# Metro_THM_LDO_Rev_B.net
KiCad netlist of a schematic drawn in EAGLE
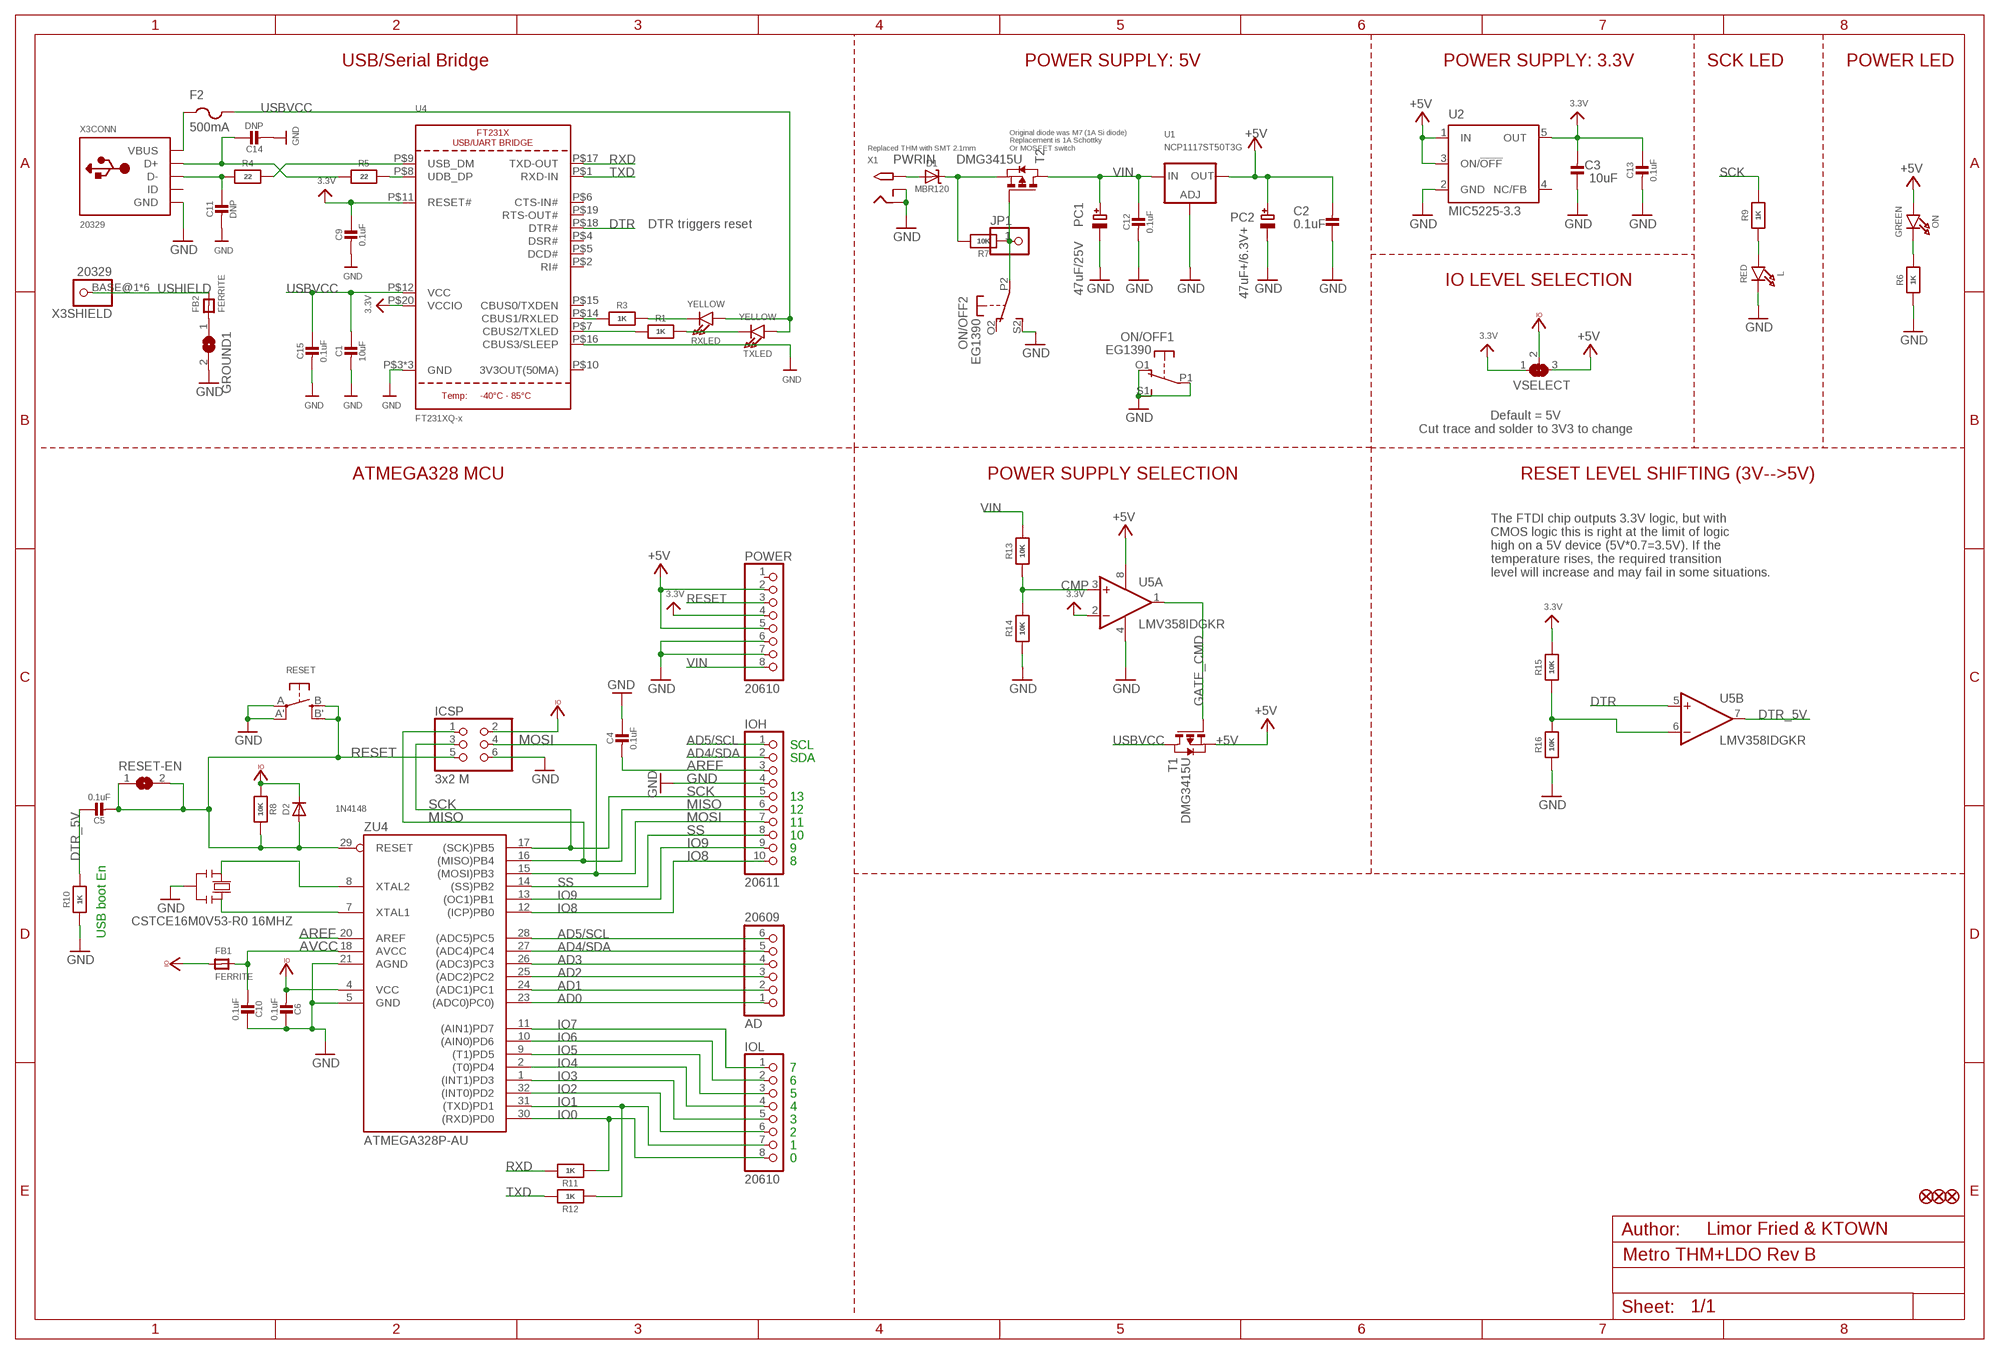
[diagram p0: schematic, sheet 1]

(export (version "E")
  (design (tool "Eeschema 10.0.6"))
  (components
    (comp (ref "AD")
      (value "20609")
      (footprint "eagle-import:1X06_OVAL")
      (libsource (lib "eagle-import") (part "HEADER-1X6"))
    )
    (comp (ref "C1")
      (value "10uF")
      (footprint "eagle-import:0805-NO")
      (libsource (lib "eagle-import") (part "CAP_CERAMIC0805-NOOUTLINE"))
    )
    (comp (ref "C2")
      (value "0.1uF")
      (footprint "eagle-import:0805-NO")
      (libsource (lib "eagle-import") (part "CAP_CERAMIC0805-NOOUTLINE"))
    )
    (comp (ref "C3")
      (value "10uF")
      (footprint "eagle-import:0805-NO")
      (libsource (lib "eagle-import") (part "CAP_CERAMIC0805-NOOUTLINE"))
    )
    (comp (ref "C4")
      (value "0.1uF")
      (footprint "eagle-import:0805-NO")
      (libsource (lib "eagle-import") (part "CAP_CERAMIC0805-NOOUTLINE"))
    )
    (comp (ref "C5")
      (value "0.1uF")
      (footprint "eagle-import:0805-NO")
      (libsource (lib "eagle-import") (part "CAP_CERAMIC0805-NOOUTLINE"))
    )
    (comp (ref "C6")
      (value "0.1uF")
      (footprint "eagle-import:0805-NO")
      (libsource (lib "eagle-import") (part "CAP_CERAMIC0805-NOOUTLINE"))
    )
    (comp (ref "C9")
      (value "0.1uF")
      (footprint "eagle-import:0805-NO")
      (libsource (lib "eagle-import") (part "CAP_CERAMIC0805-NOOUTLINE"))
    )
    (comp (ref "C10")
      (value "0.1uF")
      (footprint "eagle-import:0805_10MGAP")
      (libsource (lib "eagle-import") (part "CAP_CERAMIC0805_10MGAP"))
    )
    (comp (ref "C11")
      (value "DNP")
      (footprint "eagle-import:0805-NO")
      (libsource (lib "eagle-import") (part "CAP_CERAMIC0805-NOOUTLINE"))
    )
    (comp (ref "C12")
      (value "0.1uF")
      (footprint "eagle-import:0805-NO")
      (libsource (lib "eagle-import") (part "CAP_CERAMIC0805-NOOUTLINE"))
    )
    (comp (ref "C13")
      (value "0.1uF")
      (footprint "eagle-import:0805-NO")
      (libsource (lib "eagle-import") (part "CAP_CERAMIC0805-NOOUTLINE"))
    )
    (comp (ref "C14")
      (value "DNP")
      (footprint "eagle-import:0805-NO")
      (libsource (lib "eagle-import") (part "CAP_CERAMIC0805-NOOUTLINE"))
    )
    (comp (ref "C15")
      (value "0.1uF")
      (footprint "eagle-import:0805-NO")
      (libsource (lib "eagle-import") (part "CAP_CERAMIC0805-NOOUTLINE"))
    )
    (comp (ref "D1")
      (value "MBR120")
      (footprint "eagle-import:SOD-123")
      (libsource (lib "eagle-import") (part "DIODE-SCHOTTKYSOD-123"))
    )
    (comp (ref "D2")
      (value "1N4148")
      (footprint "eagle-import:SOD-323")
      (libsource (lib "eagle-import") (part "DIODESOD-323"))
    )
    (comp (ref "F2")
      (value "500mA")
      (footprint "eagle-import:R1206")
      (libsource (lib "eagle-import") (part "PTCFUSE-1206"))
    )
    (comp (ref "FB1")
      (value "FERRITE")
      (footprint "eagle-import:0805-NO")
      (libsource (lib "eagle-import") (part "FERRITE-0805NO"))
    )
    (comp (ref "FB2")
      (value "FERRITE")
      (footprint "eagle-import:0805-NO")
      (libsource (lib "eagle-import") (part "FERRITE-0805NO"))
    )
    (comp (ref "FD1")
      (value "FIDUCIAL\"\"")
      (footprint "eagle-import:FIDUCIAL_1MM")
      (libsource (lib "eagle-import") (part "FIDUCIAL{dblquote}{dblquote}"))
    )
    (comp (ref "FD2")
      (value "FIDUCIAL\"\"")
      (footprint "eagle-import:FIDUCIAL_1MM")
      (libsource (lib "eagle-import") (part "FIDUCIAL{dblquote}{dblquote}"))
    )
    (comp (ref "FD3")
      (value "FIDUCIAL\"\"")
      (footprint "eagle-import:FIDUCIAL_1MM")
      (libsource (lib "eagle-import") (part "FIDUCIAL{dblquote}{dblquote}"))
    )
    (comp (ref "GROUND1")
      (value "SJ")
      (footprint "eagle-import:SJ")
      (libsource (lib "eagle-import") (part "SJ"))
    )
    (comp (ref "ICSP")
      (value "3x2 M")
      (footprint "eagle-import:2X03_ROUND_70MIL")
      (libsource (lib "eagle-import") (part "HEADER-2X3"))
    )
    (comp (ref "IOH")
      (value "20611")
      (footprint "eagle-import:1X10_OVAL")
      (libsource (lib "eagle-import") (part "HEADER-1X10"))
    )
    (comp (ref "IOL")
      (value "20610")
      (footprint "eagle-import:1X08_OVAL")
      (libsource (lib "eagle-import") (part "HEADER-1X8"))
    )
    (comp (ref "JP1")
      (value "HEADER-1X1ROUND")
      (footprint "eagle-import:1X01_ROUND")
      (libsource (lib "eagle-import") (part "HEADER-1X1ROUND"))
    )
    (comp (ref "L")
      (value "RED")
      (footprint "eagle-import:CHIPLED_0805_NOOUTLINE")
      (libsource (lib "eagle-import") (part "LED0805_NOOUTLINE"))
    )
    (comp (ref "ON")
      (value "GREEN")
      (footprint "eagle-import:CHIPLED_0805_NOOUTLINE")
      (libsource (lib "eagle-import") (part "LED0805_NOOUTLINE"))
    )
    (comp (ref "ON/OFF")
      (value "EG1390")
      (footprint "eagle-import:EG1390")
      (libsource (lib "eagle-import") (part "DPDT-EG1390"))
    )
    (comp (ref "PC1")
      (value "47uF/25V")
      (footprint "eagle-import:PANASONIC_D")
      (libsource (lib "eagle-import") (part "CAP_ELECTROLYTICPANASONIC_D"))
    )
    (comp (ref "PC2")
      (value "47uF+/6.3V+")
      (footprint "eagle-import:PANASONIC_D")
      (libsource (lib "eagle-import") (part "CAP_ELECTROLYTICPANASONIC_D"))
    )
    (comp (ref "POWER")
      (value "20610")
      (footprint "eagle-import:1X08_OVAL")
      (libsource (lib "eagle-import") (part "HEADER-1X8"))
    )
    (comp (ref "R1")
      (value "1K")
      (footprint "eagle-import:0805-NO")
      (libsource (lib "eagle-import") (part "RESISTOR0805_NOOUTLINE"))
    )
    (comp (ref "R3")
      (value "1K")
      (footprint "eagle-import:0805-NO")
      (libsource (lib "eagle-import") (part "RESISTOR0805_NOOUTLINE"))
    )
    (comp (ref "R4")
      (value "22")
      (footprint "eagle-import:0805-NO")
      (libsource (lib "eagle-import") (part "RESISTOR0805_NOOUTLINE"))
    )
    (comp (ref "R5")
      (value "22")
      (footprint "eagle-import:0805-NO")
      (libsource (lib "eagle-import") (part "RESISTOR0805_NOOUTLINE"))
    )
    (comp (ref "R6")
      (value "1K")
      (footprint "eagle-import:0805-NO")
      (libsource (lib "eagle-import") (part "RESISTOR0805_NOOUTLINE"))
    )
    (comp (ref "R7")
      (value "10K")
      (footprint "eagle-import:0805-NO")
      (libsource (lib "eagle-import") (part "RESISTOR0805_NOOUTLINE"))
    )
    (comp (ref "R8")
      (value "10K")
      (footprint "eagle-import:_0805MP")
      (libsource (lib "eagle-import") (part "RESISTOR_0805MP"))
    )
    (comp (ref "R9")
      (value "1K")
      (footprint "eagle-import:0805-NO")
      (libsource (lib "eagle-import") (part "RESISTOR0805_NOOUTLINE"))
    )
    (comp (ref "R10")
      (value "1K")
      (footprint "eagle-import:0805-NO")
      (libsource (lib "eagle-import") (part "RESISTOR0805_NOOUTLINE"))
    )
    (comp (ref "R11")
      (value "1K")
      (footprint "eagle-import:0805-NO")
      (libsource (lib "eagle-import") (part "RESISTOR0805_NOOUTLINE"))
    )
    (comp (ref "R12")
      (value "1K")
      (footprint "eagle-import:0805-NO")
      (libsource (lib "eagle-import") (part "RESISTOR0805_NOOUTLINE"))
    )
    (comp (ref "R13")
      (value "10K")
      (footprint "eagle-import:0805-NO")
      (libsource (lib "eagle-import") (part "RESISTOR0805_NOOUTLINE"))
    )
    (comp (ref "R14")
      (value "10K")
      (footprint "eagle-import:0805-NO")
      (libsource (lib "eagle-import") (part "RESISTOR0805_NOOUTLINE"))
    )
    (comp (ref "R15")
      (value "10K")
      (footprint "eagle-import:0805-NO")
      (libsource (lib "eagle-import") (part "RESISTOR0805_NOOUTLINE"))
    )
    (comp (ref "R16")
      (value "10K")
      (footprint "eagle-import:0805-NO")
      (libsource (lib "eagle-import") (part "RESISTOR0805_NOOUTLINE"))
    )
    (comp (ref "RESET")
      (value "SWITCH_TACT_SMT")
      (footprint "eagle-import:EVQ-Q2")
      (libsource (lib "eagle-import") (part "SWITCH_TACT_SMT"))
    )
    (comp (ref "RESET-EN")
      (value "SJ")
      (footprint "eagle-import:SJ")
      (libsource (lib "eagle-import") (part "SJ"))
    )
    (comp (ref "RXLED")
      (value "YELLOW")
      (footprint "eagle-import:CHIPLED_0805_NOOUTLINE")
      (libsource (lib "eagle-import") (part "LED0805_NOOUTLINE"))
    )
    (comp (ref "T1")
      (value "DMG3415U")
      (footprint "eagle-import:SOT-23")
      (libsource (lib "eagle-import") (part "PMOSSOT23"))
    )
    (comp (ref "T2")
      (value "DMG3415U")
      (footprint "eagle-import:SOT-23")
      (libsource (lib "eagle-import") (part "PMOSSOT23"))
    )
    (comp (ref "TXLED")
      (value "YELLOW")
      (footprint "eagle-import:CHIPLED_0805_NOOUTLINE")
      (libsource (lib "eagle-import") (part "LED0805_NOOUTLINE"))
    )
    (comp (ref "U1")
      (value "NCP1117ST50T3G")
      (footprint "eagle-import:SOT223-R")
      (libsource (lib "eagle-import") (part "LM1117SOT223-REFLOW"))
    )
    (comp (ref "U2")
      (value "MIC5225-3.3")
      (footprint "eagle-import:SOT23-DBV")
      (libsource (lib "eagle-import") (part "LP2985-XXDBVR33"))
    )
    (comp (ref "U4")
      (value "FT231XQ-x")
      (footprint "eagle-import:QFN20_4MM")
      (libsource (lib "eagle-import") (part "FT231X"))
    )
    (comp (ref "U5")
      (value "LMV358IDGKR")
      (footprint "eagle-import:MSOP08")
      (libsource (lib "eagle-import") (part "LMV358?MMX"))
    )
    (comp (ref "VSELECT")
      (value "SOLDERJUMPER_2WAY")
      (footprint "eagle-import:SOLDERJUMPER_2WAY_OPEN_NOPASTE")
      (libsource (lib "eagle-import") (part "SOLDERJUMPER_2WAY"))
    )
    (comp (ref "X1")
      (value "2.1MMJACKSMT")
      (footprint "eagle-import:DCJACK_2MM_SMT")
      (libsource (lib "eagle-import") (part "2.1MMJACKSMT"))
    )
    (comp (ref "X3")
      (value "20329")
      (footprint "eagle-import:4UCONN_20329")
      (libsource (lib "eagle-import") (part "USB_W_SHIELD_20329"))
    )
    (comp (ref "Y2")
      (value "CSTCE16M0V53-R0 16MHZ")
      (footprint "eagle-import:RESONATOR")
      (libsource (lib "eagle-import") (part "RESONATORMU"))
    )
    (comp (ref "ZU4")
      (value "ATMEGA328P-AU")
      (footprint "eagle-import:TQFP32-08")
      (libsource (lib "eagle-import") (part "ATMEGA328P-AU"))
    )
  )
  (nets
    (net (code "1") (name "+5V") (class "Default")
      (node (ref "C2") (pin "2") (pinfunction "2_2") (pintype "passive"))
      (node (ref "ON") (pin "A") (pinfunction "A_A") (pintype "passive"))
      (node (ref "PC2") (pin "+") (pinfunction "+_+") (pintype "passive"))
      (node (ref "POWER") (pin "2") (pinfunction "2_2") (pintype "passive"))
      (node (ref "POWER") (pin "5") (pinfunction "5_5") (pintype "passive"))
      (node (ref "T1") (pin "2") (pinfunction "S_2") (pintype "passive"))
      (node (ref "U1") (pin "2") (pinfunction "OUT_2") (pintype "passive"))
      (node (ref "U1") (pin "4") (pinfunction "OUT_4") (pintype "passive"))
      (node (ref "U2") (pin "1") (pinfunction "IN_1") (pintype "input"))
      (node (ref "U2") (pin "3") (pinfunction "ON/~{OFF}_3") (pintype "input"))
      (node (ref "U5") (pin "8") (pinfunction "V+_8") (pintype "power_in"))
      (node (ref "VSELECT") (pin "3") (pinfunction "3_3") (pintype "passive"))
    )
    (net (code "2") (name "/3V3OUT(50MA)") (class "Default")
      (node (ref "U4") (pin "P$10") (pinfunction "3V3OUT(50MA)_P$10") (pintype "power_in"))
    )
    (net (code "3") (name "/AD0") (class "Default")
      (node (ref "AD") (pin "1") (pinfunction "1_1") (pintype "passive"))
      (node (ref "ZU4") (pin "23") (pinfunction "(ADC0)PC0)_23") (pintype "bidirectional"))
    )
    (net (code "4") (name "/AD1") (class "Default")
      (node (ref "AD") (pin "2") (pinfunction "2_2") (pintype "passive"))
      (node (ref "ZU4") (pin "24") (pinfunction "(ADC1)PC1_24") (pintype "bidirectional"))
    )
    (net (code "5") (name "/AD2") (class "Default")
      (node (ref "AD") (pin "3") (pinfunction "3_3") (pintype "passive"))
      (node (ref "ZU4") (pin "25") (pinfunction "(ADC2)PC2_25") (pintype "bidirectional"))
    )
    (net (code "6") (name "/AD3") (class "Default")
      (node (ref "AD") (pin "4") (pinfunction "4_4") (pintype "passive"))
      (node (ref "ZU4") (pin "26") (pinfunction "(ADC3)PC3_26") (pintype "bidirectional"))
    )
    (net (code "7") (name "/AD4{slash}SDA") (class "Default")
      (node (ref "AD") (pin "5") (pinfunction "5_5") (pintype "passive"))
      (node (ref "IOH") (pin "2") (pinfunction "2_2") (pintype "passive"))
      (node (ref "ZU4") (pin "27") (pinfunction "(ADC4)PC4_27") (pintype "bidirectional"))
    )
    (net (code "8") (name "/AD5{slash}SCL") (class "Default")
      (node (ref "AD") (pin "6") (pinfunction "6_6") (pintype "passive"))
      (node (ref "IOH") (pin "1") (pinfunction "1_1") (pintype "passive"))
      (node (ref "ZU4") (pin "28") (pinfunction "(ADC5)PC5_28") (pintype "bidirectional"))
    )
    (net (code "9") (name "/AREF") (class "Default")
      (node (ref "C4") (pin "2") (pinfunction "2_2") (pintype "passive"))
      (node (ref "IOH") (pin "3") (pinfunction "3_3") (pintype "passive"))
      (node (ref "ZU4") (pin "20") (pinfunction "AREF_20") (pintype "passive"))
    )
    (net (code "10") (name "/AVCC") (class "Default")
      (node (ref "C10") (pin "2") (pinfunction "2_2") (pintype "passive"))
      (node (ref "FB1") (pin "2") (pinfunction "P$2_2") (pintype "passive"))
      (node (ref "ZU4") (pin "18") (pinfunction "AVCC_18") (pintype "power_in"))
    )
    (net (code "11") (name "/CMP") (class "Default")
      (node (ref "R13") (pin "1") (pinfunction "1_1") (pintype "passive"))
      (node (ref "R14") (pin "2") (pinfunction "2_2") (pintype "passive"))
      (node (ref "U5") (pin "3") (pinfunction "+IN_3") (pintype "input"))
    )
    (net (code "12") (name "/DTR") (class "Default")
      (node (ref "U4") (pin "P$18") (pinfunction "DTR#_P$18") (pintype "output"))
      (node (ref "U5") (pin "5") (pinfunction "+IN_5") (pintype "input"))
    )
    (net (code "13") (name "/DTR_5V") (class "Default")
      (node (ref "C5") (pin "1") (pinfunction "1_1") (pintype "passive"))
      (node (ref "R10") (pin "2") (pinfunction "2_2") (pintype "passive"))
      (node (ref "U5") (pin "7") (pinfunction "OUT_7") (pintype "output"))
    )
    (net (code "14") (name "/GATE_CMD") (class "Default")
      (node (ref "T1") (pin "3") (pinfunction "G_3") (pintype "passive"))
      (node (ref "U5") (pin "1") (pinfunction "OUT_1") (pintype "output"))
    )
    (net (code "15") (name "/IO0") (class "Default")
      (node (ref "IOL") (pin "8") (pinfunction "8_8") (pintype "passive"))
      (node (ref "R11") (pin "1") (pinfunction "1_1") (pintype "passive"))
      (node (ref "ZU4") (pin "30") (pinfunction "(RXD)PD0_30") (pintype "bidirectional"))
    )
    (net (code "16") (name "/IO1") (class "Default")
      (node (ref "IOL") (pin "7") (pinfunction "7_7") (pintype "passive"))
      (node (ref "R12") (pin "1") (pinfunction "1_1") (pintype "passive"))
      (node (ref "ZU4") (pin "31") (pinfunction "(TXD)PD1_31") (pintype "bidirectional"))
    )
    (net (code "17") (name "/IO2") (class "Default")
      (node (ref "IOL") (pin "6") (pinfunction "6_6") (pintype "passive"))
      (node (ref "ZU4") (pin "32") (pinfunction "(INT0)PD2_32") (pintype "bidirectional"))
    )
    (net (code "18") (name "/IO3") (class "Default")
      (node (ref "IOL") (pin "5") (pinfunction "5_5") (pintype "passive"))
      (node (ref "ZU4") (pin "1") (pinfunction "(INT1)PD3_1") (pintype "bidirectional"))
    )
    (net (code "19") (name "/IO4") (class "Default")
      (node (ref "IOL") (pin "4") (pinfunction "4_4") (pintype "passive"))
      (node (ref "ZU4") (pin "2") (pinfunction "(T0)PD4_2") (pintype "bidirectional"))
    )
    (net (code "20") (name "/IO5") (class "Default")
      (node (ref "IOL") (pin "3") (pinfunction "3_3") (pintype "passive"))
      (node (ref "ZU4") (pin "9") (pinfunction "(T1)PD5_9") (pintype "bidirectional"))
    )
    (net (code "21") (name "/IO6") (class "Default")
      (node (ref "IOL") (pin "2") (pinfunction "2_2") (pintype "passive"))
      (node (ref "ZU4") (pin "10") (pinfunction "(AIN0)PD6_10") (pintype "bidirectional"))
    )
    (net (code "22") (name "/IO7") (class "Default")
      (node (ref "IOL") (pin "1") (pinfunction "1_1") (pintype "passive"))
      (node (ref "ZU4") (pin "11") (pinfunction "(AIN1)PD7_11") (pintype "bidirectional"))
    )
    (net (code "23") (name "/IO8") (class "Default")
      (node (ref "IOH") (pin "10") (pinfunction "10_10") (pintype "passive"))
      (node (ref "ZU4") (pin "12") (pinfunction "(ICP)PB0_12") (pintype "bidirectional"))
    )
    (net (code "24") (name "/IO9") (class "Default")
      (node (ref "IOH") (pin "9") (pinfunction "9_9") (pintype "passive"))
      (node (ref "ZU4") (pin "13") (pinfunction "(OC1)PB1_13") (pintype "bidirectional"))
    )
    (net (code "25") (name "/MISO") (class "Default")
      (node (ref "ICSP") (pin "1") (pinfunction "1_1") (pintype "passive"))
      (node (ref "IOH") (pin "6") (pinfunction "6_6") (pintype "passive"))
      (node (ref "ZU4") (pin "16") (pinfunction "(MISO)PB4_16") (pintype "bidirectional"))
    )
    (net (code "26") (name "/MOSI") (class "Default")
      (node (ref "ICSP") (pin "4") (pinfunction "4_4") (pintype "passive"))
      (node (ref "IOH") (pin "7") (pinfunction "7_7") (pintype "passive"))
      (node (ref "ZU4") (pin "15") (pinfunction "(MOSI)PB3_15") (pintype "bidirectional"))
    )
    (net (code "27") (name "/PWRIN") (class "Default")
      (node (ref "D1") (pin "A") (pinfunction "A_A") (pintype "passive"))
      (node (ref "X1") (pin "PWR2") (pinfunction "TIP_PWR2") (pintype "bidirectional"))
    )
    (net (code "28") (name "/RESET") (class "Default")
      (node (ref "C5") (pin "2") (pinfunction "2_2") (pintype "passive"))
      (node (ref "D2") (pin "A") (pinfunction "A_A") (pintype "passive"))
      (node (ref "ICSP") (pin "5") (pinfunction "5_5") (pintype "passive"))
      (node (ref "POWER") (pin "3") (pinfunction "3_3") (pintype "passive"))
      (node (ref "R8") (pin "1") (pinfunction "1_1") (pintype "passive"))
      (node (ref "RESET") (pin "B") (pinfunction "S_B") (pintype "passive"))
      (node (ref "RESET") (pin "B'") (pinfunction "S1_B'") (pintype "passive"))
      (node (ref "RESET-EN") (pin "1") (pinfunction "1_1") (pintype "passive"))
      (node (ref "RESET-EN") (pin "2") (pinfunction "2_2") (pintype "passive"))
      (node (ref "ZU4") (pin "29") (pinfunction "RESET_29") (pintype "input"))
    )
    (net (code "29") (name "/RXD") (class "Default")
      (node (ref "R11") (pin "2") (pinfunction "2_2") (pintype "passive"))
      (node (ref "U4") (pin "P$17") (pinfunction "TXD-OUT_P$17") (pintype "output"))
    )
    (net (code "30") (name "/SCK") (class "Default")
      (node (ref "ICSP") (pin "3") (pinfunction "3_3") (pintype "passive"))
      (node (ref "IOH") (pin "5") (pinfunction "5_5") (pintype "passive"))
      (node (ref "R9") (pin "2") (pinfunction "2_2") (pintype "passive"))
      (node (ref "ZU4") (pin "17") (pinfunction "(SCK)PB5_17") (pintype "bidirectional"))
    )
    (net (code "31") (name "/SS") (class "Default")
      (node (ref "IOH") (pin "8") (pinfunction "8_8") (pintype "passive"))
      (node (ref "ZU4") (pin "14") (pinfunction "(SS)PB2_14") (pintype "bidirectional"))
    )
    (net (code "32") (name "/TXD") (class "Default")
      (node (ref "R12") (pin "2") (pinfunction "2_2") (pintype "passive"))
      (node (ref "U4") (pin "P$1") (pinfunction "RXD-IN_P$1") (pintype "input"))
    )
    (net (code "33") (name "/USBVCC") (class "Default")
      (node (ref "C1") (pin "1") (pinfunction "1_1") (pintype "passive"))
      (node (ref "C15") (pin "1") (pinfunction "1_1") (pintype "passive"))
      (node (ref "F2") (pin "2") (pinfunction "2_2") (pintype "passive"))
      (node (ref "RXLED") (pin "A") (pinfunction "A_A") (pintype "passive"))
      (node (ref "T1") (pin "1") (pinfunction "D_1") (pintype "passive"))
      (node (ref "TXLED") (pin "A") (pinfunction "A_A") (pintype "passive"))
      (node (ref "U4") (pin "P$12") (pinfunction "VCC_P$12") (pintype "power_in"))
    )
    (net (code "34") (name "/USHIELD") (class "Default")
      (node (ref "FB2") (pin "2") (pinfunction "P$2_2") (pintype "passive"))
      (node (ref "X3") (pin "BASE@1") (pinfunction "1_BASE@1") (pintype "passive"))
      (node (ref "X3") (pin "BASE@2") (pinfunction "1_BASE@2") (pintype "passive"))
      (node (ref "X3") (pin "SPRT@1") (pinfunction "1_SPRT@1") (pintype "passive"))
      (node (ref "X3") (pin "SPRT@2") (pinfunction "1_SPRT@2") (pintype "passive"))
      (node (ref "X3") (pin "SPRT@3") (pinfunction "1_SPRT@3") (pintype "passive"))
      (node (ref "X3") (pin "SPRT@4") (pinfunction "1_SPRT@4") (pintype "passive"))
    )
    (net (code "35") (name "/VIN") (class "Default")
      (node (ref "C12") (pin "1") (pinfunction "1_1") (pintype "passive"))
      (node (ref "PC1") (pin "+") (pinfunction "+_+") (pintype "passive"))
      (node (ref "POWER") (pin "8") (pinfunction "8_8") (pintype "passive"))
      (node (ref "R13") (pin "2") (pinfunction "2_2") (pintype "passive"))
      (node (ref "T2") (pin "1") (pinfunction "D_1") (pintype "passive"))
      (node (ref "U1") (pin "3") (pinfunction "IN_3") (pintype "input"))
    )
    (net (code "36") (name "3.3V") (class "Default")
      (node (ref "C13") (pin "1") (pinfunction "1_1") (pintype "passive"))
      (node (ref "C3") (pin "2") (pinfunction "2_2") (pintype "passive"))
      (node (ref "C9") (pin "1") (pinfunction "1_1") (pintype "passive"))
      (node (ref "POWER") (pin "4") (pinfunction "4_4") (pintype "passive"))
      (node (ref "R15") (pin "2") (pinfunction "2_2") (pintype "passive"))
      (node (ref "U2") (pin "5") (pinfunction "OUT_5") (pintype "passive"))
      (node (ref "U4") (pin "P$11") (pinfunction "RESET#_P$11") (pintype "input"))
      (node (ref "U4") (pin "P$20") (pinfunction "VCCIO_P$20") (pintype "power_in"))
      (node (ref "U5") (pin "2") (pinfunction "-IN_2") (pintype "input"))
      (node (ref "VSELECT") (pin "1") (pinfunction "1_1") (pintype "passive"))
    )
    (net (code "37") (name "GND") (class "Default")
      (node (ref "C1") (pin "2") (pinfunction "2_2") (pintype "passive"))
      (node (ref "C10") (pin "1") (pinfunction "1_1") (pintype "passive"))
      (node (ref "C11") (pin "2") (pinfunction "2_2") (pintype "passive"))
      (node (ref "C12") (pin "2") (pinfunction "2_2") (pintype "passive"))
      (node (ref "C13") (pin "2") (pinfunction "2_2") (pintype "passive"))
      (node (ref "C14") (pin "2") (pinfunction "2_2") (pintype "passive"))
      (node (ref "C15") (pin "2") (pinfunction "2_2") (pintype "passive"))
      (node (ref "C2") (pin "1") (pinfunction "1_1") (pintype "passive"))
      (node (ref "C3") (pin "1") (pinfunction "1_1") (pintype "passive"))
      (node (ref "C4") (pin "1") (pinfunction "1_1") (pintype "passive"))
      (node (ref "C6") (pin "1") (pinfunction "1_1") (pintype "passive"))
      (node (ref "C9") (pin "2") (pinfunction "2_2") (pintype "passive"))
      (node (ref "GROUND1") (pin "2") (pinfunction "2_2") (pintype "passive"))
      (node (ref "ICSP") (pin "6") (pinfunction "6_6") (pintype "passive"))
      (node (ref "IOH") (pin "4") (pinfunction "4_4") (pintype "passive"))
      (node (ref "L") (pin "C") (pinfunction "C_C") (pintype "passive"))
      (node (ref "ON/OFF") (pin "O1") (pinfunction "O_O1") (pintype "passive"))
      (node (ref "ON/OFF") (pin "P1") (pinfunction "P_P1") (pintype "passive"))
      (node (ref "ON/OFF") (pin "S1") (pinfunction "S_S1") (pintype "passive"))
      (node (ref "ON/OFF") (pin "S2") (pinfunction "S_S2") (pintype "passive"))
      (node (ref "PC1") (pin "-") (pinfunction "-_-") (pintype "passive"))
      (node (ref "PC2") (pin "-") (pinfunction "-_-") (pintype "passive"))
      (node (ref "POWER") (pin "6") (pinfunction "6_6") (pintype "passive"))
      (node (ref "POWER") (pin "7") (pinfunction "7_7") (pintype "passive"))
      (node (ref "R10") (pin "1") (pinfunction "1_1") (pintype "passive"))
      (node (ref "R14") (pin "1") (pinfunction "1_1") (pintype "passive"))
      (node (ref "R16") (pin "1") (pinfunction "1_1") (pintype "passive"))
      (node (ref "R6") (pin "1") (pinfunction "1_1") (pintype "passive"))
      (node (ref "RESET") (pin "A") (pinfunction "P_A") (pintype "passive"))
      (node (ref "RESET") (pin "A'") (pinfunction "P1_A'") (pintype "passive"))
      (node (ref "U1") (pin "1") (pinfunction "ADJ_1") (pintype "input"))
      (node (ref "U2") (pin "2") (pinfunction "GND_2") (pintype "power_in"))
      (node (ref "U4") (pin "P$13") (pinfunction "GND_P$13") (pintype "power_in"))
      (node (ref "U4") (pin "P$16") (pinfunction "CBUS3/SLEEP_P$16") (pintype "bidirectional"))
      (node (ref "U4") (pin "P$21") (pinfunction "GND_P$21") (pintype "power_in"))
      (node (ref "U4") (pin "P$3") (pinfunction "GND_P$3") (pintype "power_in"))
      (node (ref "U5") (pin "4") (pinfunction "V-_4") (pintype "power_in"))
      (node (ref "X1") (pin "GND") (pinfunction "RING_GND") (pintype "bidirectional"))
      (node (ref "X1") (pin "GNDBREAK") (pinfunction "RING_SW_GNDBREAK") (pintype "bidirectional"))
      (node (ref "X3") (pin "GND") (pinfunction "GND_GND") (pintype "power_in"))
      (node (ref "Y2") (pin "2") (pinfunction "2_2") (pintype "passive"))
      (node (ref "ZU4") (pin "21") (pinfunction "AGND_21") (pintype "power_in"))
      (node (ref "ZU4") (pin "5") (pinfunction "GND_5") (pintype "power_in"))
    )
    (net (code "38") (name "Net-(C11-Pad1)") (class "Default")
      (node (ref "C11") (pin "1") (pinfunction "1_1") (pintype "passive"))
      (node (ref "R4") (pin "1") (pinfunction "1_1") (pintype "passive"))
      (node (ref "X3") (pin "D-") (pinfunction "D-_D-") (pintype "bidirectional"))
    )
    (net (code "39") (name "Net-(C14-Pad1)") (class "Default")
      (node (ref "C14") (pin "1") (pinfunction "1_1") (pintype "passive"))
      (node (ref "R5") (pin "1") (pinfunction "1_1") (pintype "passive"))
      (node (ref "X3") (pin "D+") (pinfunction "D+_D+") (pintype "bidirectional"))
    )
    (net (code "40") (name "Net-(F2-Pad1)") (class "Default")
      (node (ref "F2") (pin "1") (pinfunction "1_1") (pintype "passive"))
      (node (ref "X3") (pin "VBUS") (pinfunction "VBUS_VBUS") (pintype "power_in"))
    )
    (net (code "41") (name "Net-(FB2-P$1)") (class "Default")
      (node (ref "FB2") (pin "1") (pinfunction "P$1_1") (pintype "passive"))
      (node (ref "GROUND1") (pin "1") (pinfunction "1_1") (pintype "passive"))
    )
    (net (code "42") (name "Net-(L-PadA)") (class "Default")
      (node (ref "L") (pin "A") (pinfunction "A_A") (pintype "passive"))
      (node (ref "R9") (pin "1") (pinfunction "1_1") (pintype "passive"))
    )
    (net (code "43") (name "Net-(ON-PadC)") (class "Default")
      (node (ref "ON") (pin "C") (pinfunction "C_C") (pintype "passive"))
      (node (ref "R6") (pin "2") (pinfunction "2_2") (pintype "passive"))
    )
    (net (code "44") (name "Net-(ON/OFFB-P)") (class "Default")
      (node (ref "JP1") (pin "1") (pinfunction "1_1") (pintype "passive"))
      (node (ref "ON/OFF") (pin "P2") (pinfunction "P_P2") (pintype "passive"))
      (node (ref "R7") (pin "1") (pinfunction "1_1") (pintype "passive"))
      (node (ref "T2") (pin "3") (pinfunction "G_3") (pintype "passive"))
    )
    (net (code "45") (name "Net-(R1-Pad1)") (class "Default")
      (node (ref "R1") (pin "1") (pinfunction "1_1") (pintype "passive"))
      (node (ref "TXLED") (pin "C") (pinfunction "C_C") (pintype "passive"))
    )
    (net (code "46") (name "Net-(R3-Pad1)") (class "Default")
      (node (ref "R3") (pin "1") (pinfunction "1_1") (pintype "passive"))
      (node (ref "RXLED") (pin "C") (pinfunction "C_C") (pintype "passive"))
    )
    (net (code "47") (name "Net-(T2-S)") (class "Default")
      (node (ref "D1") (pin "C") (pinfunction "C_C") (pintype "passive"))
      (node (ref "R7") (pin "2") (pinfunction "2_2") (pintype "passive"))
      (node (ref "T2") (pin "2") (pinfunction "S_2") (pintype "passive"))
    )
    (net (code "48") (name "Net-(U4-CBUS1{slash}RXLED)") (class "Default")
      (node (ref "R3") (pin "2") (pinfunction "2_2") (pintype "passive"))
      (node (ref "U4") (pin "P$14") (pinfunction "CBUS1/RXLED_P$14") (pintype "bidirectional"))
    )
    (net (code "49") (name "Net-(U4-CBUS2{slash}TXLED)") (class "Default")
      (node (ref "R1") (pin "2") (pinfunction "2_2") (pintype "passive"))
      (node (ref "U4") (pin "P$7") (pinfunction "CBUS2/TXLED_P$7") (pintype "bidirectional"))
    )
    (net (code "50") (name "Net-(U4-UDB_DP)") (class "Default")
      (node (ref "R5") (pin "2") (pinfunction "2_2") (pintype "passive"))
      (node (ref "U4") (pin "P$8") (pinfunction "UDB_DP_P$8") (pintype "input"))
    )
    (net (code "51") (name "Net-(U4-USB_DM)") (class "Default")
      (node (ref "R4") (pin "2") (pinfunction "2_2") (pintype "passive"))
      (node (ref "U4") (pin "P$9") (pinfunction "USB_DM_P$9") (pintype "input"))
    )
    (net (code "52") (name "Net-(U5B--IN)") (class "Default")
      (node (ref "R15") (pin "1") (pinfunction "1_1") (pintype "passive"))
      (node (ref "R16") (pin "2") (pinfunction "2_2") (pintype "passive"))
      (node (ref "U5") (pin "6") (pinfunction "-IN_6") (pintype "input"))
    )
    (net (code "53") (name "Net-(ZU4-XTAL1)") (class "Default")
      (node (ref "Y2") (pin "3") (pinfunction "3_3") (pintype "passive"))
      (node (ref "ZU4") (pin "7") (pinfunction "XTAL1_7") (pintype "bidirectional"))
    )
    (net (code "54") (name "Net-(ZU4-XTAL2)") (class "Default")
      (node (ref "Y2") (pin "1") (pinfunction "1_1") (pintype "passive"))
      (node (ref "ZU4") (pin "8") (pinfunction "XTAL2_8") (pintype "bidirectional"))
    )
    (net (code "55") (name "VCCIO") (class "Default")
      (node (ref "C6") (pin "2") (pinfunction "2_2") (pintype "passive"))
      (node (ref "D2") (pin "C") (pinfunction "C_C") (pintype "passive"))
      (node (ref "FB1") (pin "1") (pinfunction "P$1_1") (pintype "passive"))
      (node (ref "ICSP") (pin "2") (pinfunction "2_2") (pintype "passive"))
      (node (ref "R8") (pin "2") (pinfunction "2_2") (pintype "passive"))
      (node (ref "VSELECT") (pin "2") (pinfunction "2_2") (pintype "passive"))
      (node (ref "ZU4") (pin "4") (pinfunction "VCC_4") (pintype "power_in"))
    )
    (net (code "56") (name "unconnected-(ON/OFFB-O-PadO2)") (class "Default")
      (node (ref "ON/OFF") (pin "O2") (pinfunction "O_O2") (pintype "passive"))
    )
    (net (code "57") (name "unconnected-(POWER-Pad1)") (class "Default")
      (node (ref "POWER") (pin "1") (pinfunction "1_1") (pintype "passive"))
    )
    (net (code "58") (name "unconnected-(U2-NC{slash}FB-Pad4)") (class "Default")
      (node (ref "U2") (pin "4") (pinfunction "NC/FB_4") (pintype "passive"))
    )
    (net (code "59") (name "unconnected-(U4-CBUS0{slash}TXDEN-PadP$15)") (class "Default")
      (node (ref "U4") (pin "P$15") (pinfunction "CBUS0/TXDEN_P$15") (pintype "bidirectional"))
    )
    (net (code "60") (name "unconnected-(U4-CTS-IN#-PadP$6)") (class "Default")
      (node (ref "U4") (pin "P$6") (pinfunction "CTS-IN#_P$6") (pintype "input"))
    )
    (net (code "61") (name "unconnected-(U4-DCD#-PadP$5)") (class "Default")
      (node (ref "U4") (pin "P$5") (pinfunction "DCD#_P$5") (pintype "input"))
    )
    (net (code "62") (name "unconnected-(U4-DSR#-PadP$4)") (class "Default")
      (node (ref "U4") (pin "P$4") (pinfunction "DSR#_P$4") (pintype "input"))
    )
    (net (code "63") (name "unconnected-(U4-RI#-PadP$2)") (class "Default")
      (node (ref "U4") (pin "P$2") (pinfunction "RI#_P$2") (pintype "input"))
    )
    (net (code "64") (name "unconnected-(U4-RTS-OUT#-PadP$19)") (class "Default")
      (node (ref "U4") (pin "P$19") (pinfunction "RTS-OUT#_P$19") (pintype "output"))
    )
    (net (code "65") (name "unconnected-(X3-PadID)") (class "Default")
      (node (ref "X3") (pin "ID") (pinfunction "ID_ID") (pintype "bidirectional"))
    )
  )
)
